# ESP32S3.net
KiCad netlist of a schematic drawn in Altium Designer
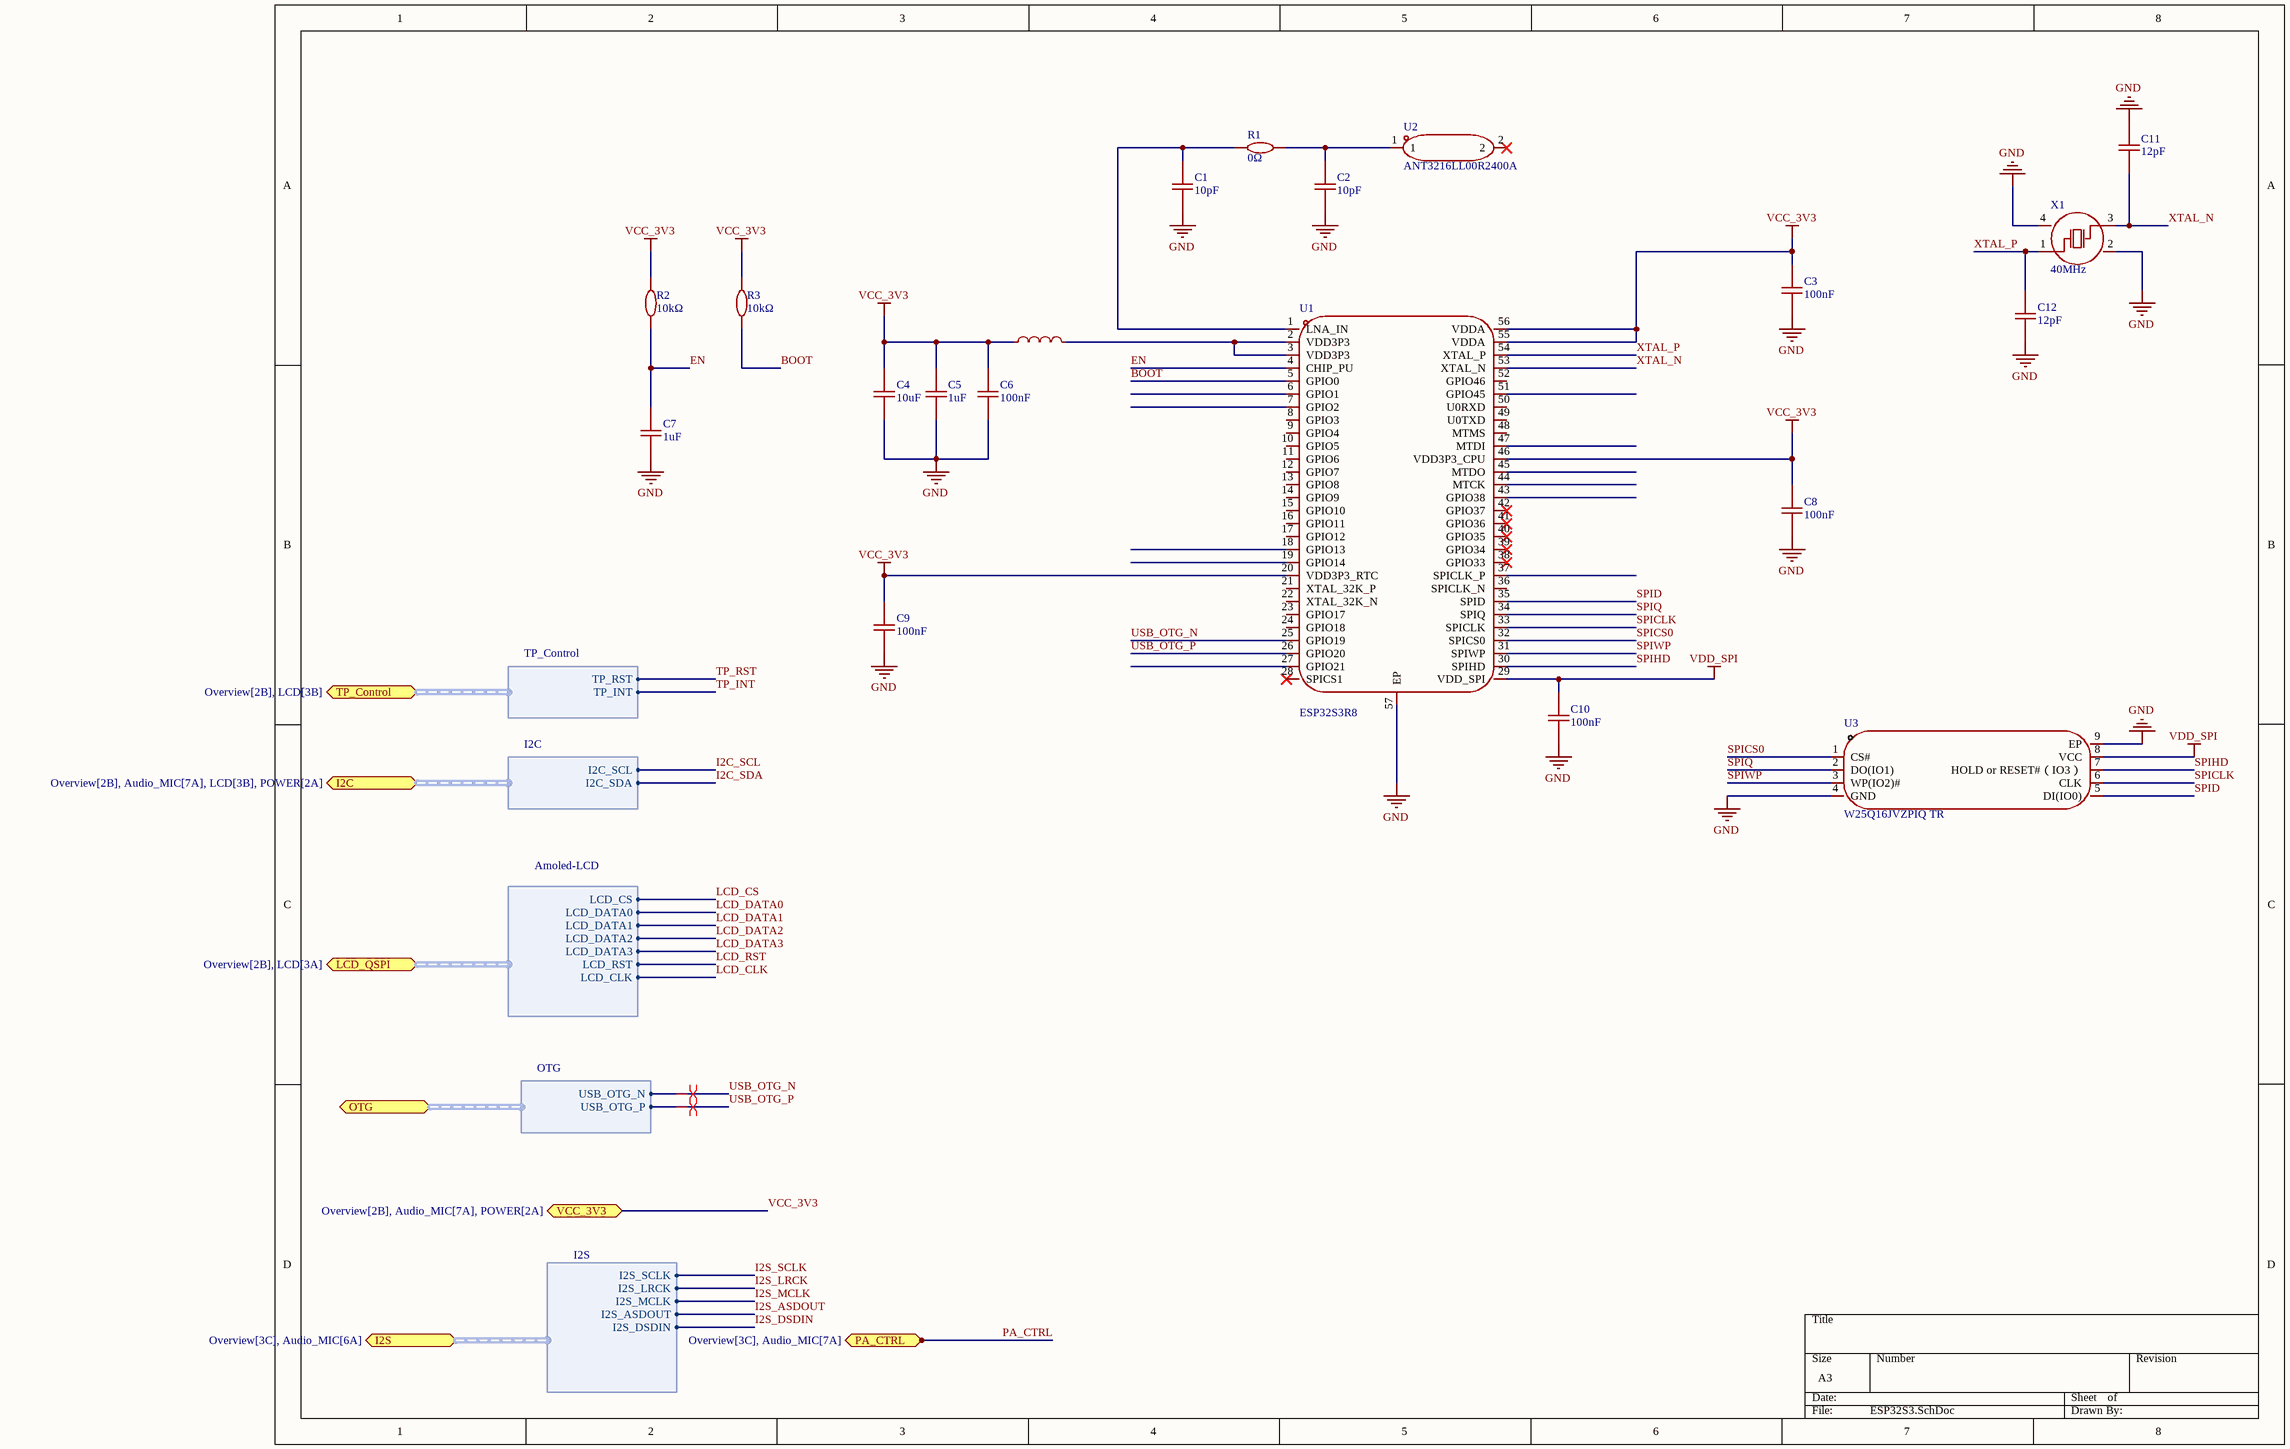
[diagram p0: ESP32S3.SchDoc]

(export (version "E")
  (design (tool "Eeschema 10.0.6"))
  (components
    (comp (ref "C1")
      (value "10pF")
      (footprint "C0402")
      (description "50V 10pF C0G ±5% 0402 Ceramic Capacitors ROHS")
      (libsource (lib "RLC") (part "10pF"))
    )
    (comp (ref "C2")
      (value "10pF")
      (footprint "C0402")
      (description "50V 10pF C0G ±5% 0402 Ceramic Capacitors ROHS")
      (libsource (lib "RLC") (part "10pF"))
    )
    (comp (ref "C3")
      (value "100nF")
      (footprint "C0402")
      (description "50V 100nF X7R ±10% 0402 Ceramic Capacitors ROHS")
      (libsource (lib "RLC") (part "100nF"))
    )
    (comp (ref "C4")
      (value "10uF")
      (footprint "C0603")
      (description "10V 10uF X5R ±10% 0603 Ceramic Capacitors ROHS")
      (libsource (lib "RLC") (part "10uF"))
    )
    (comp (ref "C5")
      (value "1uF")
      (footprint "C0402")
      (description "50V 1uF X5R ±10% 0402 Ceramic Capacitors ROHS")
      (libsource (lib "RLC") (part "1uF"))
    )
    (comp (ref "C6")
      (value "100nF")
      (footprint "C0402")
      (description "50V 100nF X7R ±10% 0402 Ceramic Capacitors ROHS")
      (libsource (lib "RLC") (part "100nF"))
    )
    (comp (ref "C7")
      (value "1uF")
      (footprint "C0402")
      (description "50V 1uF X5R ±10% 0402 Ceramic Capacitors ROHS")
      (libsource (lib "RLC") (part "1uF"))
    )
    (comp (ref "C8")
      (value "100nF")
      (footprint "C0402")
      (description "50V 100nF X7R ±10% 0402 Ceramic Capacitors ROHS")
      (libsource (lib "RLC") (part "100nF"))
    )
    (comp (ref "C9")
      (value "100nF")
      (footprint "C0402")
      (description "50V 100nF X7R ±10% 0402 Ceramic Capacitors ROHS")
      (libsource (lib "RLC") (part "100nF"))
    )
    (comp (ref "C10")
      (value "100nF")
      (footprint "C0402")
      (description "50V 100nF X7R ±10% 0402 Ceramic Capacitors ROHS")
      (libsource (lib "RLC") (part "100nF"))
    )
    (comp (ref "C11")
      (value "12pF")
      (footprint "C0402")
      (description "50V 12pF C0G ±5% 0402 Ceramic Capacitors ROHS")
      (libsource (lib "RLC") (part "12pF"))
    )
    (comp (ref "C12")
      (value "12pF")
      (footprint "C0402")
      (description "50V 12pF C0G ±5% 0402 Ceramic Capacitors ROHS")
      (libsource (lib "RLC") (part "12pF"))
    )
    (comp (ref "L1")
      (value "2nH")
      (footprint "L0402")
      (description "L0402 2nH ±0.1nH")
      (fields
        (field (name "MANUFACTURER") "Sunltech(顺磁)")
        (field (name "MANUFACTURER PART") "SLW4030S1R0NST")
      )
      (libsource (lib "RLC") (part "MLG1005S2N0BT000"))
    )
    (comp (ref "R1")
      (value "0Ω")
      (footprint "R0402")
      (description "0Ω 62.5mW 50V Thick Film Resistor ±1% 0402 Chip Resistor - Surface Mount ROHS")
      (libsource (lib "RLC") (part "0Ω"))
    )
    (comp (ref "R2")
      (value "10kΩ")
      (footprint "R0402")
      (description "62.5mW 10kΩ 50V ±100ppm/℃ Thick Film Resistor ±1% 0402 Chip Resistor - Surface Mount ROHS")
      (libsource (lib "RLC") (part "10kΩ"))
    )
    (comp (ref "R3")
      (value "10kΩ")
      (footprint "R0402")
      (description "62.5mW 10kΩ 50V ±100ppm/℃ Thick Film Resistor ±1% 0402 Chip Resistor - Surface Mount ROHS")
      (libsource (lib "RLC") (part "10kΩ"))
    )
    (comp (ref "U1")
      (value "ESP32S3R8")
      (footprint "QFN-56_L7.0-W7.0-P0.40-TL-EP4.0")
      (description "2.4GHz Wi-Fi + 低功耗蓝牙系统级芯片（SoC）")
      (libsource (lib "IC") (part "ESP32S3R8"))
    )
    (comp (ref "U2")
      (value "ANT3216LL00R2400A")
      (footprint "ANT-SMD_L3.2-W1.6")
      (libsource (lib "ANT") (part "ANT3216LL00R2400A"))
    )
    (comp (ref "U3")
      (value "W25Q16JVZPIQ TR")
      (footprint "WSON-8_L6.0-W5.0-P1.27-BL-EP")
      (description "WSON-8-EP(5x6) W25Q128JV（128M位）串行闪存为空间、引脚和电源受限的系统提供了存储解决方案。25Q系列具备灵活性和高性能。")
      (libsource (lib "IC") (part "W25Q16JVZPIQ TR"))
    )
    (comp (ref "X1")
      (value "40MHz")
      (footprint "OSC-SMD_4P-L3.2-W2.5-BL_SIT8008BI")
      (description "Crystal Oscillator 15pF SMD3225-4P Crystals ROHS")
      (libsource (lib "OSC") (part "X322540MPB4SI"))
    )
  )
  (nets
    (net (code "6") (name "/BOOT") (class "Default")
      (node (ref "R3") (pin "1") (pinfunction "1_1") (pintype "passive"))
      (node (ref "U1") (pin "5") (pinfunction "GPIO0_5") (pintype "passive"))
    )
    (net (code "7") (name "/EN") (class "Default")
      (node (ref "C7") (pin "2") (pinfunction "2_2") (pintype "passive"))
      (node (ref "R2") (pin "1") (pinfunction "1_1") (pintype "passive"))
      (node (ref "U1") (pin "4") (pinfunction "CHIP_PU_4") (pintype "passive"))
    )
    (net (code "23") (name "/SPICLK") (class "Default")
      (node (ref "U1") (pin "33") (pinfunction "SPICLK_33") (pintype "passive"))
      (node (ref "U3") (pin "6") (pinfunction "CLK_6") (pintype "passive"))
    )
    (net (code "24") (name "/SPICS0") (class "Default")
      (node (ref "U1") (pin "32") (pinfunction "SPICS0_32") (pintype "passive"))
      (node (ref "U3") (pin "1") (pinfunction "CS#_1") (pintype "passive"))
    )
    (net (code "25") (name "/SPID") (class "Default")
      (node (ref "U1") (pin "35") (pinfunction "SPID_35") (pintype "passive"))
      (node (ref "U3") (pin "5") (pinfunction "DI(IO0)_5") (pintype "passive"))
    )
    (net (code "26") (name "/SPIHD") (class "Default")
      (node (ref "U1") (pin "30") (pinfunction "SPIHD_30") (pintype "passive"))
      (node (ref "U3") (pin "7") (pinfunction "HOLD_or_RESET#（IO3）_7") (pintype "passive"))
    )
    (net (code "27") (name "/SPIQ") (class "Default")
      (node (ref "U1") (pin "34") (pinfunction "SPIQ_34") (pintype "passive"))
      (node (ref "U3") (pin "2") (pinfunction "DO(IO1)_2") (pintype "passive"))
    )
    (net (code "28") (name "/SPIWP") (class "Default")
      (node (ref "U1") (pin "31") (pinfunction "SPIWP_31") (pintype "passive"))
      (node (ref "U3") (pin "3") (pinfunction "WP(IO2)#_3") (pintype "passive"))
    )
    (net (code "31") (name "/USB_OTG_N") (class "Default")
      (node (ref "U1") (pin "25") (pinfunction "GPIO19_25") (pintype "passive"))
    )
    (net (code "32") (name "/USB_OTG_P") (class "Default")
      (node (ref "U1") (pin "26") (pinfunction "GPIO20_26") (pintype "passive"))
    )
    (net (code "33") (name "/XTAL_N") (class "Default")
      (node (ref "C11") (pin "1") (pinfunction "1_1") (pintype "passive"))
      (node (ref "U1") (pin "53") (pinfunction "XTAL_N_53") (pintype "passive"))
      (node (ref "X1") (pin "3") (pinfunction "OSC2_3") (pintype "passive"))
    )
    (net (code "34") (name "/XTAL_P") (class "Default")
      (node (ref "C12") (pin "2") (pinfunction "2_2") (pintype "passive"))
      (node (ref "U1") (pin "54") (pinfunction "XTAL_P_54") (pintype "passive"))
      (node (ref "X1") (pin "1") (pinfunction "OSC1_1") (pintype "passive"))
    )
    (net (code "40") (name "GND") (class "Default")
      (node (ref "C1") (pin "1") (pinfunction "1_1") (pintype "passive"))
      (node (ref "C10") (pin "1") (pinfunction "1_1") (pintype "passive"))
      (node (ref "C11") (pin "2") (pinfunction "2_2") (pintype "passive"))
      (node (ref "C12") (pin "1") (pinfunction "1_1") (pintype "passive"))
      (node (ref "C2") (pin "1") (pinfunction "1_1") (pintype "passive"))
      (node (ref "C3") (pin "1") (pinfunction "1_1") (pintype "passive"))
      (node (ref "C4") (pin "1") (pinfunction "1_1") (pintype "passive"))
      (node (ref "C5") (pin "1") (pinfunction "1_1") (pintype "passive"))
      (node (ref "C6") (pin "1") (pinfunction "1_1") (pintype "passive"))
      (node (ref "C7") (pin "1") (pinfunction "1_1") (pintype "passive"))
      (node (ref "C8") (pin "1") (pinfunction "1_1") (pintype "passive"))
      (node (ref "C9") (pin "1") (pinfunction "1_1") (pintype "passive"))
      (node (ref "U1") (pin "57") (pinfunction "EP_57") (pintype "passive"))
      (node (ref "U3") (pin "4") (pinfunction "GND_4") (pintype "passive"))
      (node (ref "U3") (pin "9") (pinfunction "EP_9") (pintype "passive"))
      (node (ref "X1") (pin "2") (pinfunction "GND_2") (pintype "passive"))
      (node (ref "X1") (pin "4") (pinfunction "GND_4") (pintype "passive"))
    )
    (net (code "41") (name "Net-(C2-Pad2)") (class "Default")
      (node (ref "C2") (pin "2") (pinfunction "2_2") (pintype "passive"))
      (node (ref "R1") (pin "2") (pinfunction "2_2") (pintype "passive"))
      (node (ref "U2") (pin "1") (pinfunction "1_1") (pintype "passive"))
    )
    (net (code "42") (name "Net-(L1-Pad2)") (class "Default")
      (node (ref "L1") (pin "2") (pinfunction "2_2") (pintype "passive"))
      (node (ref "U1") (pin "2") (pinfunction "VDD3P3_2") (pintype "passive"))
      (node (ref "U1") (pin "3") (pinfunction "VDD3P3_3") (pintype "passive"))
    )
    (net (code "43") (name "Net-(U1-LNA_IN)") (class "Default")
      (node (ref "C1") (pin "2") (pinfunction "2_2") (pintype "passive"))
      (node (ref "R1") (pin "1") (pinfunction "1_1") (pintype "passive"))
      (node (ref "U1") (pin "1") (pinfunction "LNA_IN_1") (pintype "passive"))
    )
    (net (code "44") (name "VCC_3V3") (class "Default")
      (node (ref "C3") (pin "2") (pinfunction "2_2") (pintype "passive"))
      (node (ref "C4") (pin "2") (pinfunction "2_2") (pintype "passive"))
      (node (ref "C5") (pin "2") (pinfunction "2_2") (pintype "passive"))
      (node (ref "C6") (pin "2") (pinfunction "2_2") (pintype "passive"))
      (node (ref "C8") (pin "2") (pinfunction "2_2") (pintype "passive"))
      (node (ref "C9") (pin "2") (pinfunction "2_2") (pintype "passive"))
      (node (ref "L1") (pin "1") (pinfunction "1_1") (pintype "passive"))
      (node (ref "R2") (pin "2") (pinfunction "2_2") (pintype "passive"))
      (node (ref "R3") (pin "2") (pinfunction "2_2") (pintype "passive"))
      (node (ref "U1") (pin "20") (pinfunction "VDD3P3_RTC_20") (pintype "passive"))
      (node (ref "U1") (pin "46") (pinfunction "VDD3P3_CPU_46") (pintype "passive"))
      (node (ref "U1") (pin "55") (pinfunction "VDDA_55") (pintype "passive"))
      (node (ref "U1") (pin "56") (pinfunction "VDDA_56") (pintype "passive"))
    )
    (net (code "45") (name "VDD_SPI") (class "Default")
      (node (ref "C10") (pin "2") (pinfunction "2_2") (pintype "passive"))
      (node (ref "U1") (pin "29") (pinfunction "VDD_SPI_29") (pintype "passive"))
      (node (ref "U3") (pin "8") (pinfunction "VCC_8") (pintype "passive"))
    )
    (net (code "46") (name "unconnected-(U1-GPIO1-Pad6)") (class "Default")
      (node (ref "U1") (pin "6") (pinfunction "GPIO1_6") (pintype "passive"))
    )
    (net (code "47") (name "unconnected-(U1-GPIO2-Pad7)") (class "Default")
      (node (ref "U1") (pin "7") (pinfunction "GPIO2_7") (pintype "passive"))
    )
    (net (code "48") (name "unconnected-(U1-GPIO3-Pad8)") (class "Default")
      (node (ref "U1") (pin "8") (pinfunction "GPIO3_8") (pintype "passive"))
    )
    (net (code "49") (name "unconnected-(U1-GPIO4-Pad9)") (class "Default")
      (node (ref "U1") (pin "9") (pinfunction "GPIO4_9") (pintype "passive"))
    )
    (net (code "50") (name "unconnected-(U1-GPIO5-Pad10)") (class "Default")
      (node (ref "U1") (pin "10") (pinfunction "GPIO5_10") (pintype "passive"))
    )
    (net (code "51") (name "unconnected-(U1-GPIO6-Pad11)") (class "Default")
      (node (ref "U1") (pin "11") (pinfunction "GPIO6_11") (pintype "passive"))
    )
    (net (code "52") (name "unconnected-(U1-GPIO7-Pad12)") (class "Default")
      (node (ref "U1") (pin "12") (pinfunction "GPIO7_12") (pintype "passive"))
    )
    (net (code "53") (name "unconnected-(U1-GPIO8-Pad13)") (class "Default")
      (node (ref "U1") (pin "13") (pinfunction "GPIO8_13") (pintype "passive"))
    )
    (net (code "54") (name "unconnected-(U1-GPIO9-Pad14)") (class "Default")
      (node (ref "U1") (pin "14") (pinfunction "GPIO9_14") (pintype "passive"))
    )
    (net (code "55") (name "unconnected-(U1-GPIO10-Pad15)") (class "Default")
      (node (ref "U1") (pin "15") (pinfunction "GPIO10_15") (pintype "passive"))
    )
    (net (code "56") (name "unconnected-(U1-GPIO11-Pad16)") (class "Default")
      (node (ref "U1") (pin "16") (pinfunction "GPIO11_16") (pintype "passive"))
    )
    (net (code "57") (name "unconnected-(U1-GPIO12-Pad17)") (class "Default")
      (node (ref "U1") (pin "17") (pinfunction "GPIO12_17") (pintype "passive"))
    )
    (net (code "58") (name "unconnected-(U1-GPIO13-Pad18)") (class "Default")
      (node (ref "U1") (pin "18") (pinfunction "GPIO13_18") (pintype "passive"))
    )
    (net (code "59") (name "unconnected-(U1-GPIO14-Pad19)") (class "Default")
      (node (ref "U1") (pin "19") (pinfunction "GPIO14_19") (pintype "passive"))
    )
    (net (code "60") (name "unconnected-(U1-GPIO17-Pad23)") (class "Default")
      (node (ref "U1") (pin "23") (pinfunction "GPIO17_23") (pintype "passive"))
    )
    (net (code "61") (name "unconnected-(U1-GPIO18-Pad24)") (class "Default")
      (node (ref "U1") (pin "24") (pinfunction "GPIO18_24") (pintype "passive"))
    )
    (net (code "62") (name "unconnected-(U1-GPIO21-Pad27)") (class "Default")
      (node (ref "U1") (pin "27") (pinfunction "GPIO21_27") (pintype "passive"))
    )
    (net (code "63") (name "unconnected-(U1-GPIO33-Pad38)") (class "Default")
      (node (ref "U1") (pin "38") (pinfunction "GPIO33_38") (pintype "passive+no_connect"))
    )
    (net (code "64") (name "unconnected-(U1-GPIO34-Pad39)") (class "Default")
      (node (ref "U1") (pin "39") (pinfunction "GPIO34_39") (pintype "passive+no_connect"))
    )
    (net (code "65") (name "unconnected-(U1-GPIO35-Pad40)") (class "Default")
      (node (ref "U1") (pin "40") (pinfunction "GPIO35_40") (pintype "passive+no_connect"))
    )
    (net (code "66") (name "unconnected-(U1-GPIO36-Pad41)") (class "Default")
      (node (ref "U1") (pin "41") (pinfunction "GPIO36_41") (pintype "passive+no_connect"))
    )
    (net (code "67") (name "unconnected-(U1-GPIO37-Pad42)") (class "Default")
      (node (ref "U1") (pin "42") (pinfunction "GPIO37_42") (pintype "passive+no_connect"))
    )
    (net (code "68") (name "unconnected-(U1-GPIO38-Pad43)") (class "Default")
      (node (ref "U1") (pin "43") (pinfunction "GPIO38_43") (pintype "passive"))
    )
    (net (code "69") (name "unconnected-(U1-GPIO45-Pad51)") (class "Default")
      (node (ref "U1") (pin "51") (pinfunction "GPIO45_51") (pintype "passive"))
    )
    (net (code "70") (name "unconnected-(U1-GPIO46-Pad52)") (class "Default")
      (node (ref "U1") (pin "52") (pinfunction "GPIO46_52") (pintype "passive"))
    )
    (net (code "71") (name "unconnected-(U1-MTCK-Pad44)") (class "Default")
      (node (ref "U1") (pin "44") (pinfunction "MTCK_44") (pintype "passive"))
    )
    (net (code "72") (name "unconnected-(U1-MTDI-Pad47)") (class "Default")
      (node (ref "U1") (pin "47") (pinfunction "MTDI_47") (pintype "passive"))
    )
    (net (code "73") (name "unconnected-(U1-MTDO-Pad45)") (class "Default")
      (node (ref "U1") (pin "45") (pinfunction "MTDO_45") (pintype "passive"))
    )
    (net (code "74") (name "unconnected-(U1-MTMS-Pad48)") (class "Default")
      (node (ref "U1") (pin "48") (pinfunction "MTMS_48") (pintype "passive"))
    )
    (net (code "75") (name "unconnected-(U1-SPICLK_N-Pad36)") (class "Default")
      (node (ref "U1") (pin "36") (pinfunction "SPICLK_N_36") (pintype "passive"))
    )
    (net (code "76") (name "unconnected-(U1-SPICLK_P-Pad37)") (class "Default")
      (node (ref "U1") (pin "37") (pinfunction "SPICLK_P_37") (pintype "passive"))
    )
    (net (code "77") (name "unconnected-(U1-SPICS1-Pad28)") (class "Default")
      (node (ref "U1") (pin "28") (pinfunction "SPICS1_28") (pintype "passive+no_connect"))
    )
    (net (code "78") (name "unconnected-(U1-U0RXD-Pad50)") (class "Default")
      (node (ref "U1") (pin "50") (pinfunction "U0RXD_50") (pintype "passive"))
    )
    (net (code "79") (name "unconnected-(U1-U0TXD-Pad49)") (class "Default")
      (node (ref "U1") (pin "49") (pinfunction "U0TXD_49") (pintype "passive"))
    )
    (net (code "80") (name "unconnected-(U1-XTAL_32K_N-Pad22)") (class "Default")
      (node (ref "U1") (pin "22") (pinfunction "XTAL_32K_N_22") (pintype "passive"))
    )
    (net (code "81") (name "unconnected-(U1-XTAL_32K_P-Pad21)") (class "Default")
      (node (ref "U1") (pin "21") (pinfunction "XTAL_32K_P_21") (pintype "passive"))
    )
    (net (code "82") (name "unconnected-(U2-Pad2)") (class "Default")
      (node (ref "U2") (pin "2") (pinfunction "2_2") (pintype "passive+no_connect"))
    )
  )
)
